# PowerPlayground.net
KiCad netlist of a schematic drawn in EAGLE
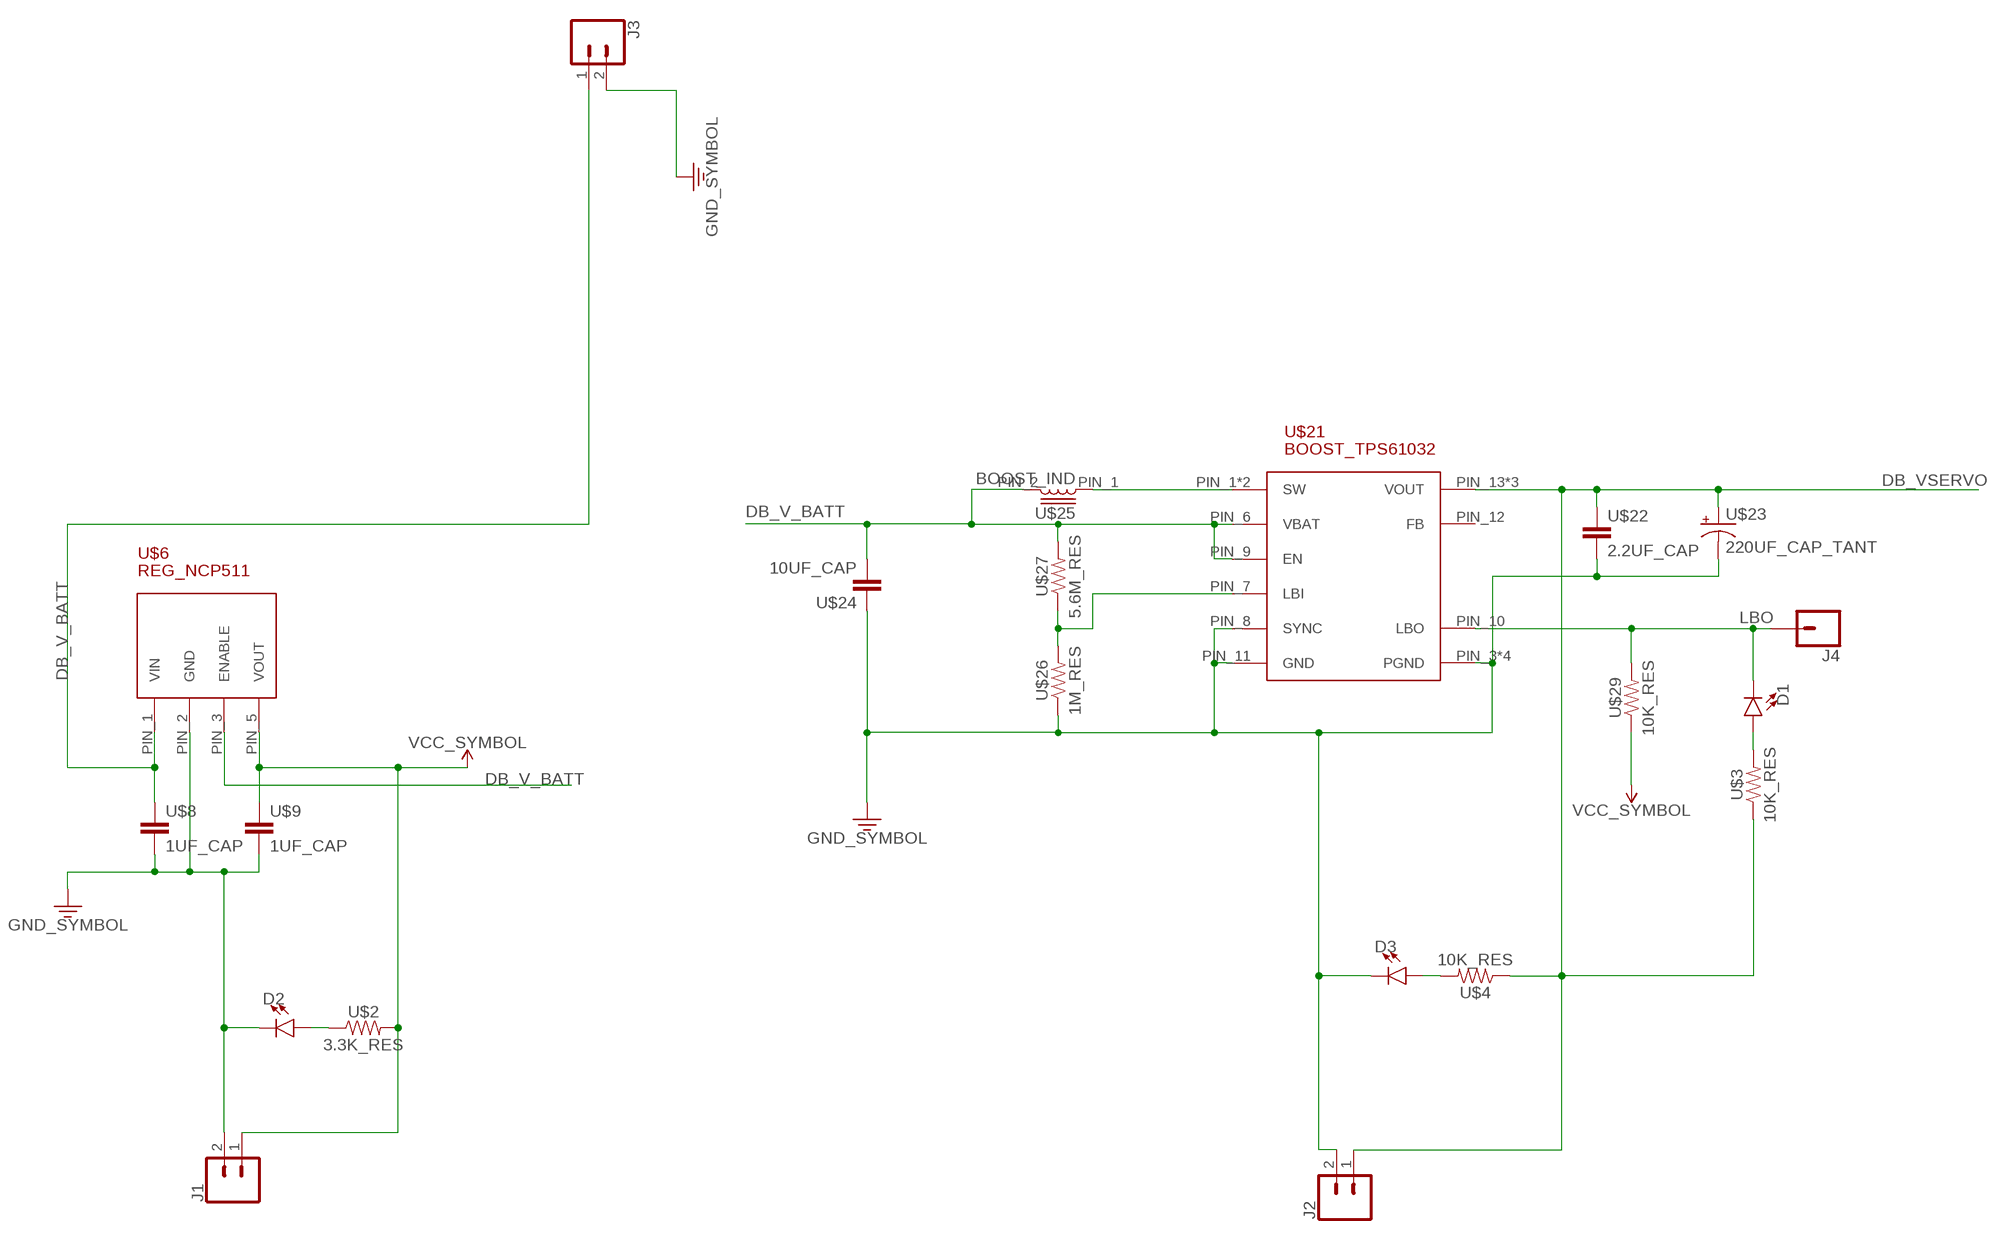
[diagram p0: schematic, sheet 1]

(export (version "E")
  (design (tool "Eeschema 10.0.6"))
  (components
    (comp (ref "D1")
      (value "LED5MM")
      (footprint "eagle-import:LED_5MM")
      (libsource (lib "eagle-import") (part "LED5MM"))
    )
    (comp (ref "D2")
      (value "LED5MM")
      (footprint "eagle-import:LED_5MM")
      (libsource (lib "eagle-import") (part "LED5MM"))
    )
    (comp (ref "D3")
      (value "LED5MM")
      (footprint "eagle-import:LED_5MM")
      (libsource (lib "eagle-import") (part "LED5MM"))
    )
    (comp (ref "J1")
      (value "CONN_02PTH3")
      (footprint "eagle-import:1X02_LONGPADS")
      (libsource (lib "eagle-import") (part "CONN_02PTH3"))
    )
    (comp (ref "J2")
      (value "CONN_02PTH3")
      (footprint "eagle-import:1X02_LONGPADS")
      (libsource (lib "eagle-import") (part "CONN_02PTH3"))
    )
    (comp (ref "J3")
      (value "CONN_02PTH3")
      (footprint "eagle-import:1X02_LONGPADS")
      (libsource (lib "eagle-import") (part "CONN_02PTH3"))
    )
    (comp (ref "J4")
      (value "CONN_01OFFSET")
      (footprint "eagle-import:1X01_OFFSET")
      (libsource (lib "eagle-import") (part "CONN_01OFFSET"))
    )
    (comp (ref "U$2")
      (value "3.3K_RES")
      (footprint "eagle-import:0603")
      (libsource (lib "eagle-import") (part "3.3K_RES"))
    )
    (comp (ref "U$3")
      (value "10K_RES")
      (footprint "eagle-import:0603")
      (libsource (lib "eagle-import") (part "10K_RES"))
    )
    (comp (ref "U$4")
      (value "10K_RES")
      (footprint "eagle-import:0603")
      (libsource (lib "eagle-import") (part "10K_RES"))
    )
    (comp (ref "U$6")
      (value "REG_NCP511")
      (footprint "eagle-import:TSOP-5")
      (libsource (lib "eagle-import") (part "REG_NCP511"))
    )
    (comp (ref "U$8")
      (value "1UF_CAP")
      (footprint "eagle-import:0603")
      (libsource (lib "eagle-import") (part "1UF_CAP"))
    )
    (comp (ref "U$9")
      (value "1UF_CAP")
      (footprint "eagle-import:0603")
      (libsource (lib "eagle-import") (part "1UF_CAP"))
    )
    (comp (ref "U$21")
      (value "BOOST_TPS61032")
      (footprint "eagle-import:PWP-16")
      (libsource (lib "eagle-import") (part "BOOST_TPS61032"))
    )
    (comp (ref "U$22")
      (value "2.2UF_CAP")
      (footprint "eagle-import:0603")
      (libsource (lib "eagle-import") (part "2.2UF_CAP"))
    )
    (comp (ref "U$23")
      (value "220UF_CAP_TANT")
      (footprint "eagle-import:7343")
      (libsource (lib "eagle-import") (part "220UF_CAP_TANT"))
    )
    (comp (ref "U$24")
      (value "10UF_CAP")
      (footprint "eagle-import:0603")
      (libsource (lib "eagle-import") (part "10UF_CAP"))
    )
    (comp (ref "U$25")
      (value "BOOST_IND")
      (footprint "eagle-import:VLS6045EX")
      (libsource (lib "eagle-import") (part "BOOST_IND"))
    )
    (comp (ref "U$26")
      (value "1M_RES")
      (footprint "eagle-import:0603")
      (libsource (lib "eagle-import") (part "1M_RES"))
    )
    (comp (ref "U$27")
      (value "5.6M_RES")
      (footprint "eagle-import:0603")
      (libsource (lib "eagle-import") (part "5.6M_RES"))
    )
    (comp (ref "U$29")
      (value "10K_RES")
      (footprint "eagle-import:0603")
      (libsource (lib "eagle-import") (part "10K_RES"))
    )
  )
  (nets
    (net (code "1") (name "/DB_VSERVO") (class "Default")
      (node (ref "J2") (pin "1") (pinfunction "1_1") (pintype "passive"))
      (node (ref "U$21") (pin "PIN_13") (pinfunction "VOUT_PIN_13") (pintype "bidirectional"))
      (node (ref "U$21") (pin "PIN_14") (pinfunction "VOUT_PIN_14") (pintype "bidirectional"))
      (node (ref "U$21") (pin "PIN_15") (pinfunction "VOUT_PIN_15") (pintype "bidirectional"))
      (node (ref "U$22") (pin "1") (pinfunction "1_1") (pintype "passive"))
      (node (ref "U$23") (pin "PIN_2_+") (pinfunction "+_PIN_2_+") (pintype "passive"))
      (node (ref "U$3") (pin "1") (pinfunction "1_1") (pintype "passive"))
      (node (ref "U$4") (pin "1") (pinfunction "1_1") (pintype "passive"))
    )
    (net (code "2") (name "/DB_V_BATT") (class "Default")
      (node (ref "J3") (pin "1") (pinfunction "1_1") (pintype "passive"))
      (node (ref "U$21") (pin "PIN_6") (pinfunction "VBAT_PIN_6") (pintype "bidirectional"))
      (node (ref "U$21") (pin "PIN_9") (pinfunction "EN_PIN_9") (pintype "bidirectional"))
      (node (ref "U$24") (pin "2") (pinfunction "2_2") (pintype "passive"))
      (node (ref "U$25") (pin "PIN_2") (pinfunction "PIN_2_PIN_2") (pintype "passive"))
      (node (ref "U$27") (pin "2") (pinfunction "2_2") (pintype "passive"))
      (node (ref "U$6") (pin "PIN_1") (pinfunction "VIN_PIN_1") (pintype "bidirectional"))
      (node (ref "U$6") (pin "PIN_3") (pinfunction "ENABLE_PIN_3") (pintype "bidirectional"))
      (node (ref "U$8") (pin "1") (pinfunction "1_1") (pintype "passive"))
    )
    (net (code "3") (name "/LBO") (class "Default")
      (node (ref "D1") (pin "K") (pinfunction "C_K") (pintype "passive"))
      (node (ref "J4") (pin "1") (pinfunction "1_1") (pintype "passive"))
      (node (ref "U$21") (pin "PIN_10") (pinfunction "LBO_PIN_10") (pintype "bidirectional"))
      (node (ref "U$29") (pin "2") (pinfunction "2_2") (pintype "passive"))
    )
    (net (code "4") (name "GND_SYMBOL") (class "Default")
      (node (ref "D2") (pin "K") (pinfunction "C_K") (pintype "passive"))
      (node (ref "D3") (pin "K") (pinfunction "C_K") (pintype "passive"))
      (node (ref "J1") (pin "2") (pinfunction "2_2") (pintype "passive"))
      (node (ref "J2") (pin "2") (pinfunction "2_2") (pintype "passive"))
      (node (ref "J3") (pin "2") (pinfunction "2_2") (pintype "passive"))
      (node (ref "U$21") (pin "PIN_11") (pinfunction "GND_PIN_11") (pintype "bidirectional"))
      (node (ref "U$21") (pin "PIN_17") (pinfunction "PGND_PIN_17") (pintype "bidirectional"))
      (node (ref "U$21") (pin "PIN_3") (pinfunction "PGND_PIN_3") (pintype "bidirectional"))
      (node (ref "U$21") (pin "PIN_4") (pinfunction "PGND_PIN_4") (pintype "bidirectional"))
      (node (ref "U$21") (pin "PIN_5") (pinfunction "PGND_PIN_5") (pintype "bidirectional"))
      (node (ref "U$21") (pin "PIN_8") (pinfunction "SYNC_PIN_8") (pintype "bidirectional"))
      (node (ref "U$22") (pin "2") (pinfunction "2_2") (pintype "passive"))
      (node (ref "U$23") (pin "PIN_1_-") (pinfunction "-_PIN_1_-") (pintype "passive"))
      (node (ref "U$24") (pin "1") (pinfunction "1_1") (pintype "passive"))
      (node (ref "U$26") (pin "1") (pinfunction "1_1") (pintype "passive"))
      (node (ref "U$6") (pin "PIN_2") (pinfunction "GND_PIN_2") (pintype "bidirectional"))
      (node (ref "U$8") (pin "2") (pinfunction "2_2") (pintype "passive"))
      (node (ref "U$9") (pin "2") (pinfunction "2_2") (pintype "passive"))
    )
    (net (code "5") (name "Net-(D1-PadA)") (class "Default")
      (node (ref "D1") (pin "A") (pinfunction "A_A") (pintype "passive"))
      (node (ref "U$3") (pin "2") (pinfunction "2_2") (pintype "passive"))
    )
    (net (code "6") (name "Net-(D2-PadA)") (class "Default")
      (node (ref "D2") (pin "A") (pinfunction "A_A") (pintype "passive"))
      (node (ref "U$2") (pin "1") (pinfunction "1_1") (pintype "passive"))
    )
    (net (code "7") (name "Net-(D3-PadA)") (class "Default")
      (node (ref "D3") (pin "A") (pinfunction "A_A") (pintype "passive"))
      (node (ref "U$4") (pin "2") (pinfunction "2_2") (pintype "passive"))
    )
    (net (code "8") (name "Net-(U$21-LBI)") (class "Default")
      (node (ref "U$21") (pin "PIN_7") (pinfunction "LBI_PIN_7") (pintype "bidirectional"))
      (node (ref "U$26") (pin "2") (pinfunction "2_2") (pintype "passive"))
      (node (ref "U$27") (pin "1") (pinfunction "1_1") (pintype "passive"))
    )
    (net (code "9") (name "Net-(U$21-SW-PadPIN_1)") (class "Default")
      (node (ref "U$21") (pin "PIN_1") (pinfunction "SW_PIN_1") (pintype "bidirectional"))
      (node (ref "U$21") (pin "PIN_2") (pinfunction "SW_PIN_2") (pintype "bidirectional"))
      (node (ref "U$25") (pin "PIN_1") (pinfunction "PIN_1_PIN_1") (pintype "passive"))
    )
    (net (code "10") (name "VCC_SYMBOL") (class "Default")
      (node (ref "J1") (pin "1") (pinfunction "1_1") (pintype "passive"))
      (node (ref "U$2") (pin "2") (pinfunction "2_2") (pintype "passive"))
      (node (ref "U$29") (pin "1") (pinfunction "1_1") (pintype "passive"))
      (node (ref "U$6") (pin "PIN_5") (pinfunction "VOUT_PIN_5") (pintype "bidirectional"))
      (node (ref "U$9") (pin "1") (pinfunction "1_1") (pintype "passive"))
    )
    (net (code "11") (name "unconnected-(U$21-FB-PadPIN_12)") (class "Default")
      (node (ref "U$21") (pin "PIN_12") (pinfunction "FB_PIN_12") (pintype "bidirectional"))
    )
  )
)
